# mb1225.net
KiCad netlist of a schematic drawn in Altium Designer
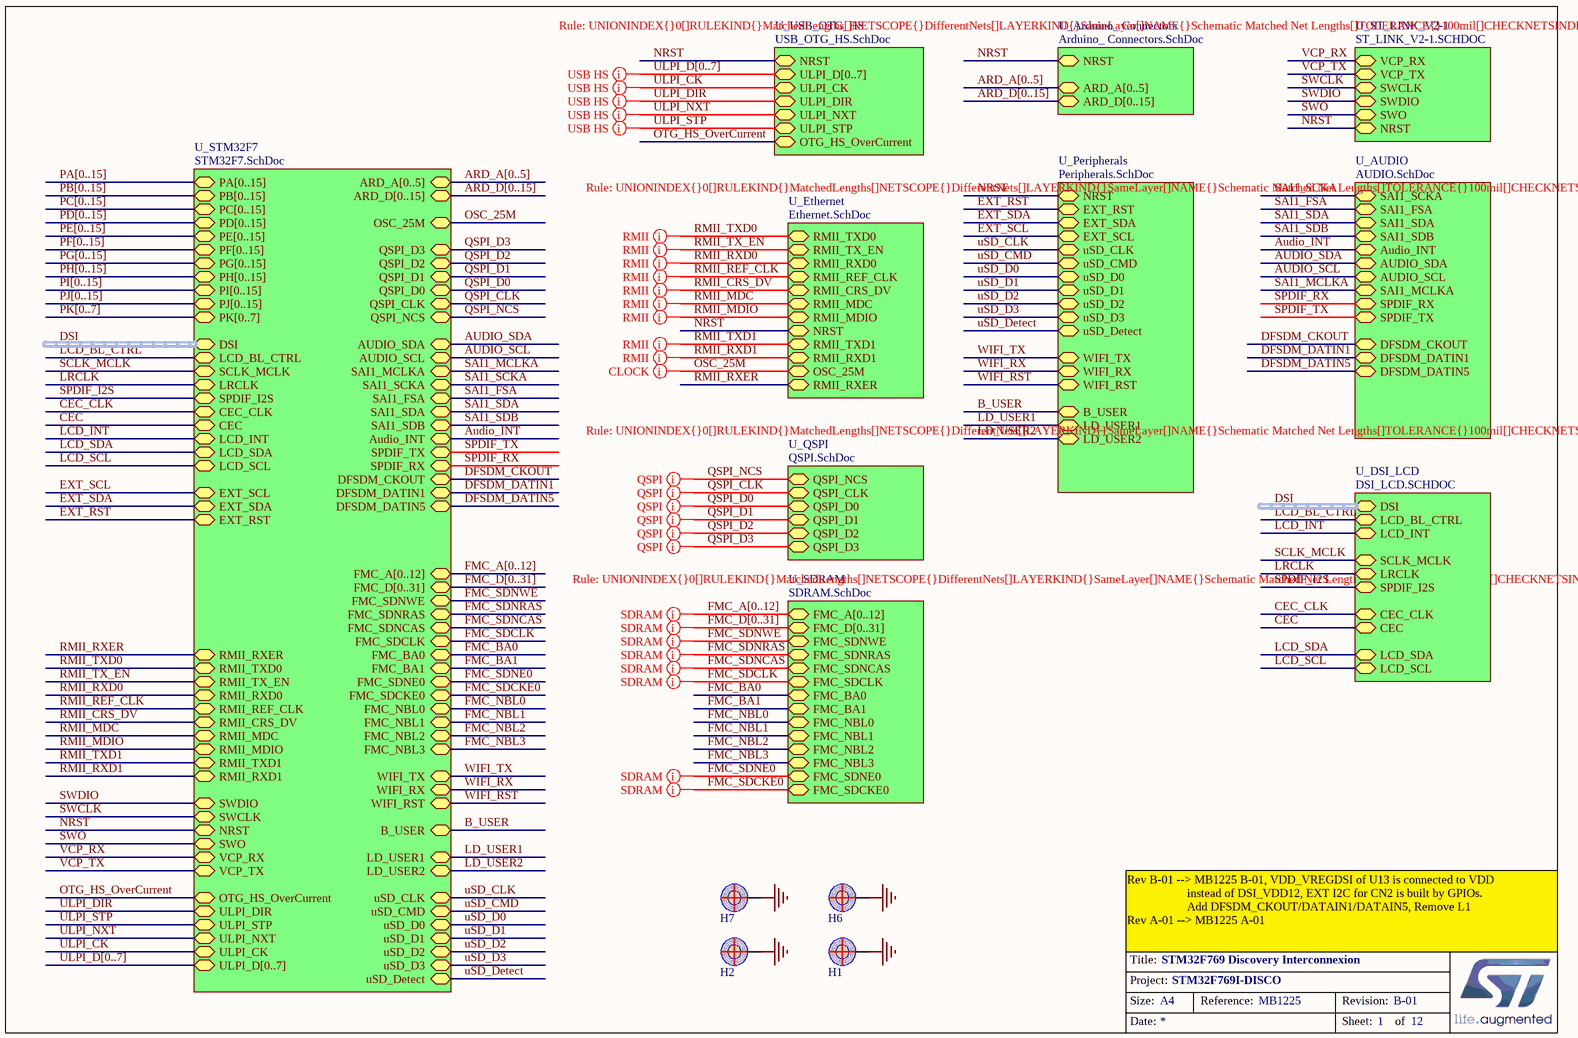
[diagram p0: mb1225.SchDoc]

(export (version "E")
  (design (tool "Eeschema 10.0.6"))
  (components
    (comp (ref "H1")
      (value "POSITION HOLE C6D3R5")
      (footprint "HOLE_C6D3R5")
      (libsource (lib "MCD_TOOLS_MISCELLANEOUS") (part "POSITION HOLE C6D3R5"))
    )
    (comp (ref "H2")
      (value "POSITION HOLE C6D3R5")
      (footprint "HOLE_C6D3R5")
      (libsource (lib "MCD_TOOLS_MISCELLANEOUS") (part "POSITION HOLE C6D3R5"))
    )
    (comp (ref "H6")
      (value "POSITION HOLE C6D3R5")
      (footprint "HOLE_C6D3R5")
      (libsource (lib "MCD_TOOLS_MISCELLANEOUS") (part "POSITION HOLE C6D3R5"))
    )
    (comp (ref "H7")
      (value "POSITION HOLE C6D3R5")
      (footprint "HOLE_C6D3R5")
      (libsource (lib "MCD_TOOLS_MISCELLANEOUS") (part "POSITION HOLE C6D3R5"))
    )
  )
  (nets
    (net (code "340") (name "GND") (class "Default")
      (node (ref "H1") (pin "1") (pinfunction "1_1") (pintype "passive"))
      (node (ref "H2") (pin "1") (pinfunction "1_1") (pintype "passive"))
      (node (ref "H6") (pin "1") (pinfunction "1_1") (pintype "passive"))
      (node (ref "H7") (pin "1") (pinfunction "1_1") (pintype "passive"))
    )
  )
)
